# rokit.net
KiCad netlist of a schematic drawn in EAGLE
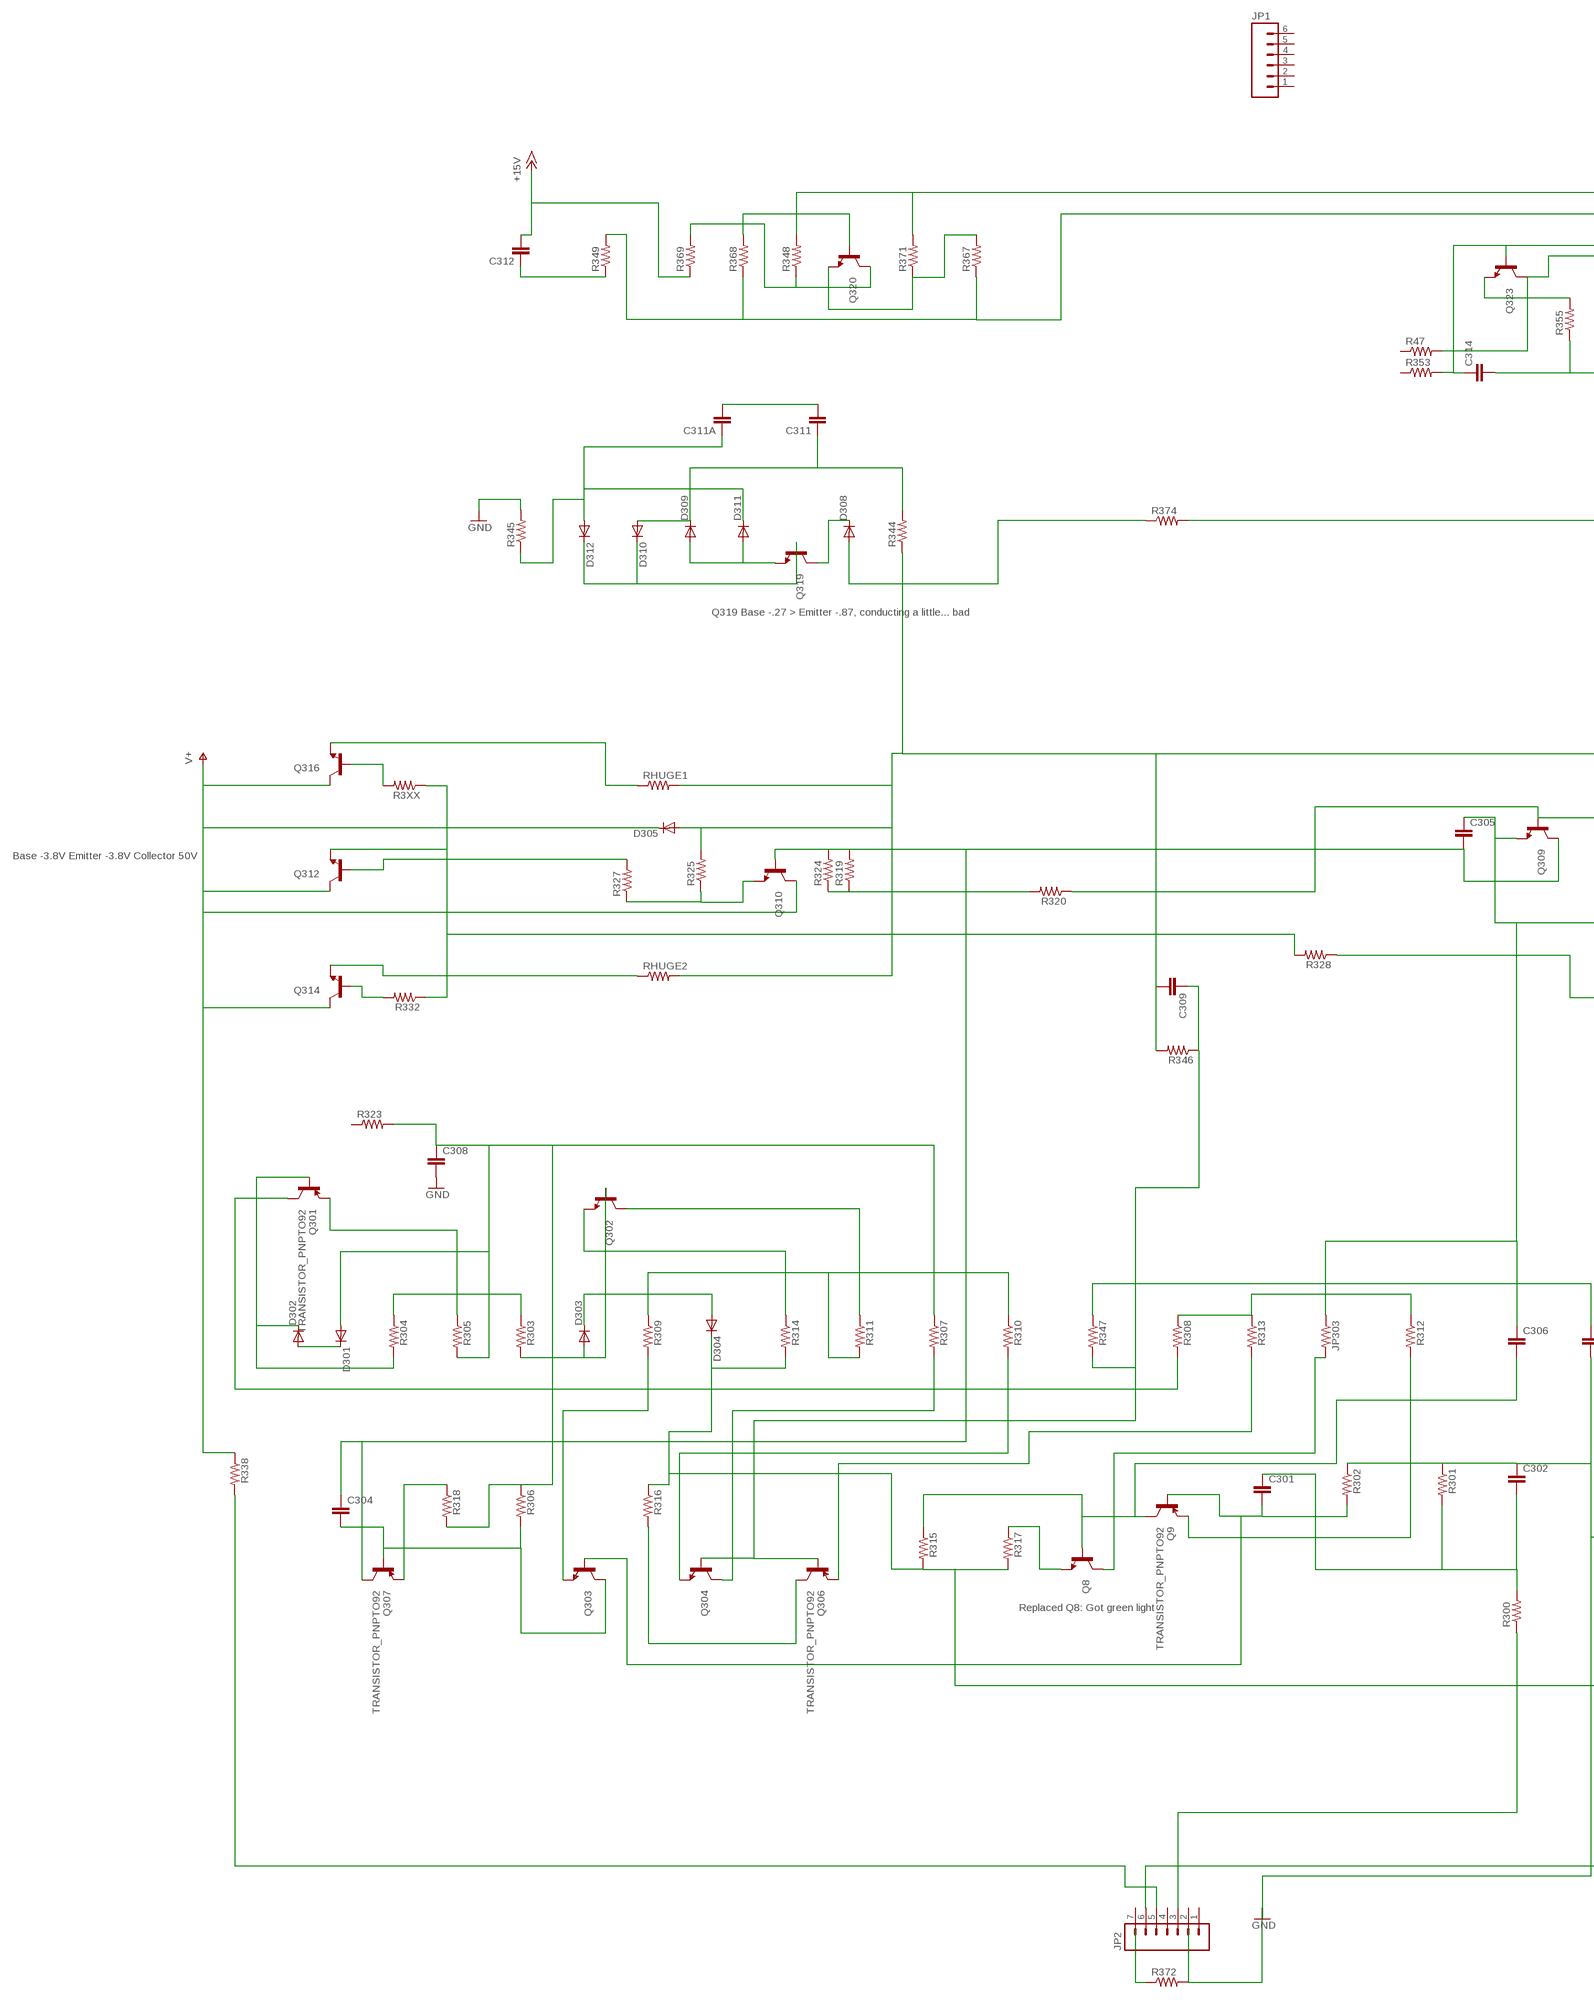
[diagram p0: schematic, sheet 1, part 1 of 2]
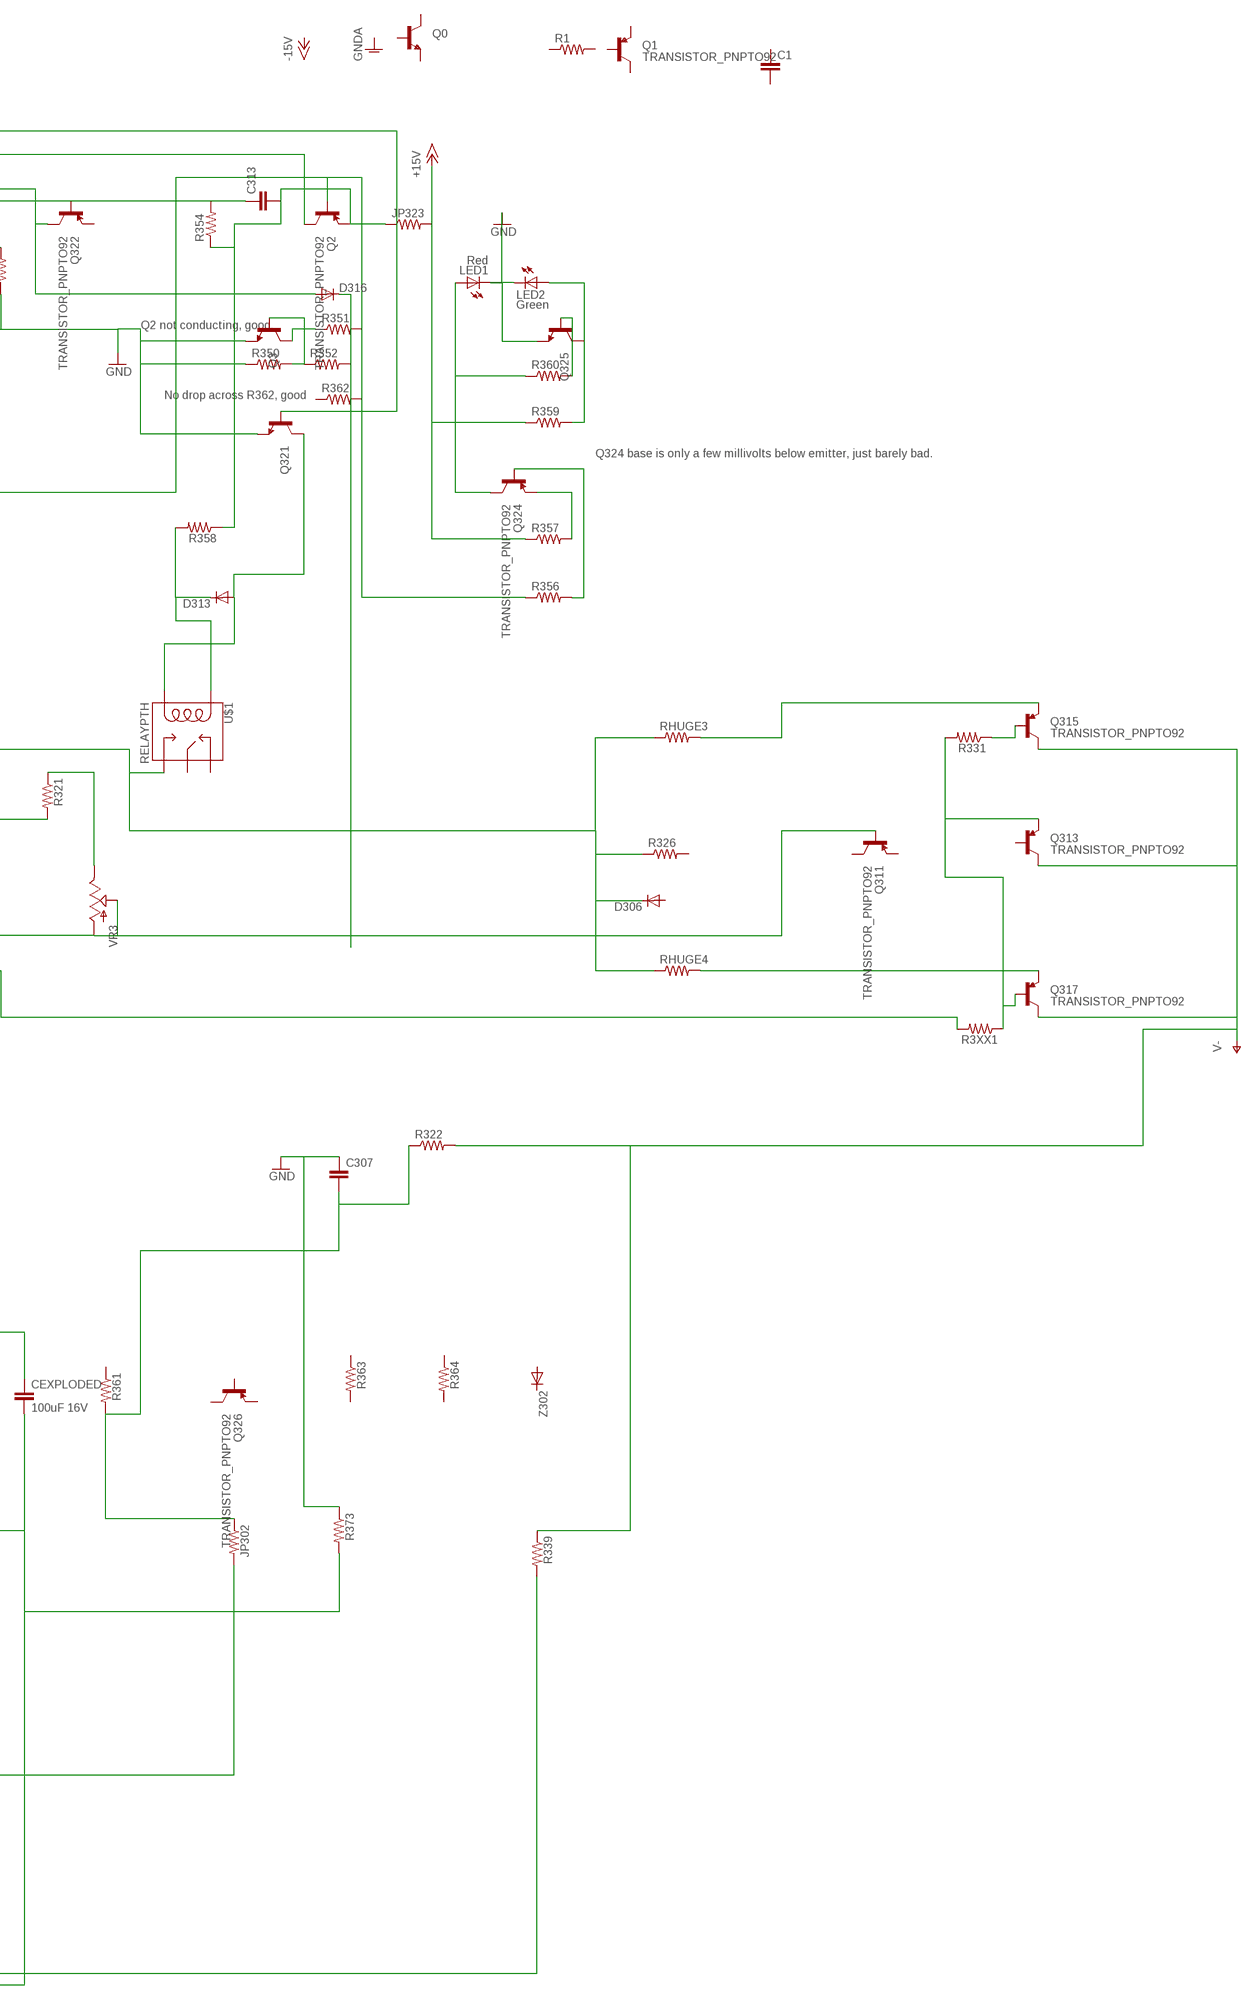
[diagram p1: schematic, sheet 1, part 2 of 2]

(export (version "E")
  (design (tool "Eeschema 10.0.6"))
  (components
    (comp (ref "C1")
      (value "CAPPTH")
      (footprint "eagle-import:CAP-PTH-SMALL")
      (libsource (lib "eagle-import") (part "CAPPTH"))
    )
    (comp (ref "C301")
      (value "CAPPTH")
      (footprint "eagle-import:CAP-PTH-SMALL")
      (libsource (lib "eagle-import") (part "CAPPTH"))
    )
    (comp (ref "C302")
      (value "CAPPTH")
      (footprint "eagle-import:CAP-PTH-SMALL")
      (libsource (lib "eagle-import") (part "CAPPTH"))
    )
    (comp (ref "C304")
      (value "CAPPTH")
      (footprint "eagle-import:CAP-PTH-SMALL")
      (libsource (lib "eagle-import") (part "CAPPTH"))
    )
    (comp (ref "C305")
      (value "CAPPTH")
      (footprint "eagle-import:CAP-PTH-SMALL")
      (libsource (lib "eagle-import") (part "CAPPTH"))
    )
    (comp (ref "C306")
      (value "CAPPTH")
      (footprint "eagle-import:CAP-PTH-SMALL")
      (libsource (lib "eagle-import") (part "CAPPTH"))
    )
    (comp (ref "C307")
      (value "CAPPTH")
      (footprint "eagle-import:CAP-PTH-SMALL")
      (libsource (lib "eagle-import") (part "CAPPTH"))
    )
    (comp (ref "C308")
      (value "CAPPTH")
      (footprint "eagle-import:CAP-PTH-SMALL")
      (libsource (lib "eagle-import") (part "CAPPTH"))
    )
    (comp (ref "C309")
      (value "CAPPTH")
      (footprint "eagle-import:CAP-PTH-SMALL")
      (libsource (lib "eagle-import") (part "CAPPTH"))
    )
    (comp (ref "C311")
      (value "CAPPTH")
      (footprint "eagle-import:CAP-PTH-SMALL")
      (libsource (lib "eagle-import") (part "CAPPTH"))
    )
    (comp (ref "C311A")
      (value "CAPPTH")
      (footprint "eagle-import:CAP-PTH-SMALL")
      (libsource (lib "eagle-import") (part "CAPPTH"))
    )
    (comp (ref "C312")
      (value "CAPPTH")
      (footprint "eagle-import:CAP-PTH-SMALL")
      (libsource (lib "eagle-import") (part "CAPPTH"))
    )
    (comp (ref "C313")
      (value "CAPPTH")
      (footprint "eagle-import:CAP-PTH-SMALL")
      (libsource (lib "eagle-import") (part "CAPPTH"))
    )
    (comp (ref "C314")
      (value "CAPPTH")
      (footprint "eagle-import:CAP-PTH-SMALL")
      (libsource (lib "eagle-import") (part "CAPPTH"))
    )
    (comp (ref "CEXPLODED")
      (value "100uF 16V")
      (footprint "eagle-import:CAP-PTH-SMALL")
      (libsource (lib "eagle-import") (part "CAPPTH"))
    )
    (comp (ref "D301")
      (value "DIODE1N4148")
      (footprint "eagle-import:DIODE-1N4148")
      (libsource (lib "eagle-import") (part "DIODE1N4148"))
    )
    (comp (ref "D302")
      (value "DIODE1N4148")
      (footprint "eagle-import:DIODE-1N4148")
      (libsource (lib "eagle-import") (part "DIODE1N4148"))
    )
    (comp (ref "D303")
      (value "DIODE1N4148")
      (footprint "eagle-import:DIODE-1N4148")
      (libsource (lib "eagle-import") (part "DIODE1N4148"))
    )
    (comp (ref "D304")
      (value "DIODE1N4148")
      (footprint "eagle-import:DIODE-1N4148")
      (libsource (lib "eagle-import") (part "DIODE1N4148"))
    )
    (comp (ref "D305")
      (value "DIODE1N4148")
      (footprint "eagle-import:DIODE-1N4148")
      (libsource (lib "eagle-import") (part "DIODE1N4148"))
    )
    (comp (ref "D306")
      (value "DIODE1N4148")
      (footprint "eagle-import:DIODE-1N4148")
      (libsource (lib "eagle-import") (part "DIODE1N4148"))
    )
    (comp (ref "D308")
      (value "DIODE1N4148")
      (footprint "eagle-import:DIODE-1N4148")
      (libsource (lib "eagle-import") (part "DIODE1N4148"))
    )
    (comp (ref "D309")
      (value "DIODE1N4148")
      (footprint "eagle-import:DIODE-1N4148")
      (libsource (lib "eagle-import") (part "DIODE1N4148"))
    )
    (comp (ref "D310")
      (value "DIODE1N4148")
      (footprint "eagle-import:DIODE-1N4148")
      (libsource (lib "eagle-import") (part "DIODE1N4148"))
    )
    (comp (ref "D311")
      (value "DIODE1N4148")
      (footprint "eagle-import:DIODE-1N4148")
      (libsource (lib "eagle-import") (part "DIODE1N4148"))
    )
    (comp (ref "D312")
      (value "DIODE1N4148")
      (footprint "eagle-import:DIODE-1N4148")
      (libsource (lib "eagle-import") (part "DIODE1N4148"))
    )
    (comp (ref "D313")
      (value "DIODE1N4148")
      (footprint "eagle-import:DIODE-1N4148")
      (libsource (lib "eagle-import") (part "DIODE1N4148"))
    )
    (comp (ref "D316")
      (value "DIODE1N4148")
      (footprint "eagle-import:DIODE-1N4148")
      (libsource (lib "eagle-import") (part "DIODE1N4148"))
    )
    (comp (ref "JP1")
      (value "M06LONGPADS")
      (footprint "eagle-import:1X06_LONGPADS")
      (libsource (lib "eagle-import") (part "M06LONGPADS"))
    )
    (comp (ref "JP2")
      (value "M07")
      (footprint "eagle-import:1X07")
      (libsource (lib "eagle-import") (part "M07"))
    )
    (comp (ref "JP302")
      (value "RESISTORPTH-1/4W")
      (footprint "eagle-import:AXIAL-0.4")
      (libsource (lib "eagle-import") (part "RESISTORPTH-1/4W"))
    )
    (comp (ref "JP303")
      (value "RESISTORPTH-1/4W")
      (footprint "eagle-import:AXIAL-0.4")
      (libsource (lib "eagle-import") (part "RESISTORPTH-1/4W"))
    )
    (comp (ref "JP323")
      (value "RESISTORPTH-1/4W")
      (footprint "eagle-import:AXIAL-0.4")
      (libsource (lib "eagle-import") (part "RESISTORPTH-1/4W"))
    )
    (comp (ref "LED1")
      (value "Red")
      (footprint "eagle-import:LED5MM")
      (libsource (lib "eagle-import") (part "LED5MM"))
    )
    (comp (ref "LED2")
      (value "Green")
      (footprint "eagle-import:LED5MM")
      (libsource (lib "eagle-import") (part "LED5MM"))
    )
    (comp (ref "Q0")
      (value "TRANSISTOR_NPNTO92")
      (footprint "eagle-import:TO-92")
      (libsource (lib "eagle-import") (part "TRANSISTOR_NPNTO92"))
    )
    (comp (ref "Q1")
      (value "TRANSISTOR_PNPTO92")
      (footprint "eagle-import:TO-92")
      (libsource (lib "eagle-import") (part "TRANSISTOR_PNPTO92"))
    )
    (comp (ref "Q2")
      (value "TRANSISTOR_PNPTO92")
      (footprint "eagle-import:TO-92")
      (libsource (lib "eagle-import") (part "TRANSISTOR_PNPTO92"))
    )
    (comp (ref "Q3")
      (value "TRANSISTOR_NPNTO92")
      (footprint "eagle-import:TO-92")
      (libsource (lib "eagle-import") (part "TRANSISTOR_NPNTO92"))
    )
    (comp (ref "Q8")
      (value "TRANSISTOR_NPNTO92")
      (footprint "eagle-import:TO-92")
      (libsource (lib "eagle-import") (part "TRANSISTOR_NPNTO92"))
    )
    (comp (ref "Q9")
      (value "TRANSISTOR_PNPTO92")
      (footprint "eagle-import:TO-92")
      (libsource (lib "eagle-import") (part "TRANSISTOR_PNPTO92"))
    )
    (comp (ref "Q301")
      (value "TRANSISTOR_PNPTO92")
      (footprint "eagle-import:TO-92")
      (libsource (lib "eagle-import") (part "TRANSISTOR_PNPTO92"))
    )
    (comp (ref "Q302")
      (value "TRANSISTOR_NPNTO92")
      (footprint "eagle-import:TO-92")
      (libsource (lib "eagle-import") (part "TRANSISTOR_NPNTO92"))
    )
    (comp (ref "Q303")
      (value "TRANSISTOR_NPNTO92")
      (footprint "eagle-import:TO-92")
      (libsource (lib "eagle-import") (part "TRANSISTOR_NPNTO92"))
    )
    (comp (ref "Q304")
      (value "TRANSISTOR_NPNTO92")
      (footprint "eagle-import:TO-92")
      (libsource (lib "eagle-import") (part "TRANSISTOR_NPNTO92"))
    )
    (comp (ref "Q306")
      (value "TRANSISTOR_PNPTO92")
      (footprint "eagle-import:TO-92")
      (libsource (lib "eagle-import") (part "TRANSISTOR_PNPTO92"))
    )
    (comp (ref "Q307")
      (value "TRANSISTOR_PNPTO92")
      (footprint "eagle-import:TO-92")
      (libsource (lib "eagle-import") (part "TRANSISTOR_PNPTO92"))
    )
    (comp (ref "Q309")
      (value "TRANSISTOR_NPNTO92")
      (footprint "eagle-import:TO-92")
      (libsource (lib "eagle-import") (part "TRANSISTOR_NPNTO92"))
    )
    (comp (ref "Q310")
      (value "TRANSISTOR_NPNTO92")
      (footprint "eagle-import:TO-92")
      (libsource (lib "eagle-import") (part "TRANSISTOR_NPNTO92"))
    )
    (comp (ref "Q311")
      (value "TRANSISTOR_PNPTO92")
      (footprint "eagle-import:TO-92")
      (libsource (lib "eagle-import") (part "TRANSISTOR_PNPTO92"))
    )
    (comp (ref "Q312")
      (value "TRANSISTOR_NPNTO92")
      (footprint "eagle-import:TO-92")
      (libsource (lib "eagle-import") (part "TRANSISTOR_NPNTO92"))
    )
    (comp (ref "Q313")
      (value "TRANSISTOR_PNPTO92")
      (footprint "eagle-import:TO-92")
      (libsource (lib "eagle-import") (part "TRANSISTOR_PNPTO92"))
    )
    (comp (ref "Q314")
      (value "TRANSISTOR_NPNTO92")
      (footprint "eagle-import:TO-92")
      (libsource (lib "eagle-import") (part "TRANSISTOR_NPNTO92"))
    )
    (comp (ref "Q315")
      (value "TRANSISTOR_PNPTO92")
      (footprint "eagle-import:TO-92")
      (libsource (lib "eagle-import") (part "TRANSISTOR_PNPTO92"))
    )
    (comp (ref "Q316")
      (value "TRANSISTOR_NPNTO92")
      (footprint "eagle-import:TO-92")
      (libsource (lib "eagle-import") (part "TRANSISTOR_NPNTO92"))
    )
    (comp (ref "Q317")
      (value "TRANSISTOR_PNPTO92")
      (footprint "eagle-import:TO-92")
      (libsource (lib "eagle-import") (part "TRANSISTOR_PNPTO92"))
    )
    (comp (ref "Q319")
      (value "TRANSISTOR_NPNTO92")
      (footprint "eagle-import:TO-92")
      (libsource (lib "eagle-import") (part "TRANSISTOR_NPNTO92"))
    )
    (comp (ref "Q320")
      (value "TRANSISTOR_NPNTO92")
      (footprint "eagle-import:TO-92")
      (libsource (lib "eagle-import") (part "TRANSISTOR_NPNTO92"))
    )
    (comp (ref "Q321")
      (value "TRANSISTOR_NPNTO92")
      (footprint "eagle-import:TO-92")
      (libsource (lib "eagle-import") (part "TRANSISTOR_NPNTO92"))
    )
    (comp (ref "Q322")
      (value "TRANSISTOR_PNPTO92")
      (footprint "eagle-import:TO-92")
      (libsource (lib "eagle-import") (part "TRANSISTOR_PNPTO92"))
    )
    (comp (ref "Q323")
      (value "TRANSISTOR_NPNTO92")
      (footprint "eagle-import:TO-92")
      (libsource (lib "eagle-import") (part "TRANSISTOR_NPNTO92"))
    )
    (comp (ref "Q324")
      (value "TRANSISTOR_PNPTO92")
      (footprint "eagle-import:TO-92")
      (libsource (lib "eagle-import") (part "TRANSISTOR_PNPTO92"))
    )
    (comp (ref "Q325")
      (value "TRANSISTOR_NPNTO92")
      (footprint "eagle-import:TO-92")
      (libsource (lib "eagle-import") (part "TRANSISTOR_NPNTO92"))
    )
    (comp (ref "Q326")
      (value "TRANSISTOR_PNPTO92")
      (footprint "eagle-import:TO-92")
      (libsource (lib "eagle-import") (part "TRANSISTOR_PNPTO92"))
    )
    (comp (ref "R1")
      (value "RESISTORPTH-1/4W")
      (footprint "eagle-import:AXIAL-0.4")
      (libsource (lib "eagle-import") (part "RESISTORPTH-1/4W"))
    )
    (comp (ref "R3XX")
      (value "RESISTORPTH-1/4W")
      (footprint "eagle-import:AXIAL-0.4")
      (libsource (lib "eagle-import") (part "RESISTORPTH-1/4W"))
    )
    (comp (ref "R3XX1")
      (value "RESISTORPTH-1/4W")
      (footprint "eagle-import:AXIAL-0.4")
      (libsource (lib "eagle-import") (part "RESISTORPTH-1/4W"))
    )
    (comp (ref "R47")
      (value "RESISTORPTH-1/4W")
      (footprint "eagle-import:AXIAL-0.4")
      (libsource (lib "eagle-import") (part "RESISTORPTH-1/4W"))
    )
    (comp (ref "R300")
      (value "RESISTORPTH-1/4W")
      (footprint "eagle-import:AXIAL-0.4")
      (libsource (lib "eagle-import") (part "RESISTORPTH-1/4W"))
    )
    (comp (ref "R301")
      (value "RESISTORPTH-1/4W")
      (footprint "eagle-import:AXIAL-0.4")
      (libsource (lib "eagle-import") (part "RESISTORPTH-1/4W"))
    )
    (comp (ref "R302")
      (value "RESISTORPTH-1/4W")
      (footprint "eagle-import:AXIAL-0.4")
      (libsource (lib "eagle-import") (part "RESISTORPTH-1/4W"))
    )
    (comp (ref "R303")
      (value "RESISTORPTH-1/4W")
      (footprint "eagle-import:AXIAL-0.4")
      (libsource (lib "eagle-import") (part "RESISTORPTH-1/4W"))
    )
    (comp (ref "R304")
      (value "RESISTORPTH-1/4W")
      (footprint "eagle-import:AXIAL-0.4")
      (libsource (lib "eagle-import") (part "RESISTORPTH-1/4W"))
    )
    (comp (ref "R305")
      (value "RESISTORPTH-1/4W")
      (footprint "eagle-import:AXIAL-0.4")
      (libsource (lib "eagle-import") (part "RESISTORPTH-1/4W"))
    )
    (comp (ref "R306")
      (value "RESISTORPTH-1/4W")
      (footprint "eagle-import:AXIAL-0.4")
      (libsource (lib "eagle-import") (part "RESISTORPTH-1/4W"))
    )
    (comp (ref "R307")
      (value "RESISTORPTH-1/4W")
      (footprint "eagle-import:AXIAL-0.4")
      (libsource (lib "eagle-import") (part "RESISTORPTH-1/4W"))
    )
    (comp (ref "R308")
      (value "RESISTORPTH-1/4W")
      (footprint "eagle-import:AXIAL-0.4")
      (libsource (lib "eagle-import") (part "RESISTORPTH-1/4W"))
    )
    (comp (ref "R309")
      (value "RESISTORPTH-1/4W")
      (footprint "eagle-import:AXIAL-0.4")
      (libsource (lib "eagle-import") (part "RESISTORPTH-1/4W"))
    )
    (comp (ref "R310")
      (value "RESISTORPTH-1/4W")
      (footprint "eagle-import:AXIAL-0.4")
      (libsource (lib "eagle-import") (part "RESISTORPTH-1/4W"))
    )
    (comp (ref "R311")
      (value "RESISTORPTH-1/4W")
      (footprint "eagle-import:AXIAL-0.4")
      (libsource (lib "eagle-import") (part "RESISTORPTH-1/4W"))
    )
    (comp (ref "R312")
      (value "RESISTORPTH-1/4W")
      (footprint "eagle-import:AXIAL-0.4")
      (libsource (lib "eagle-import") (part "RESISTORPTH-1/4W"))
    )
    (comp (ref "R313")
      (value "RESISTORPTH-1/4W")
      (footprint "eagle-import:AXIAL-0.4")
      (libsource (lib "eagle-import") (part "RESISTORPTH-1/4W"))
    )
    (comp (ref "R314")
      (value "RESISTORPTH-1/4W")
      (footprint "eagle-import:AXIAL-0.4")
      (libsource (lib "eagle-import") (part "RESISTORPTH-1/4W"))
    )
    (comp (ref "R315")
      (value "RESISTORPTH-1/4W")
      (footprint "eagle-import:AXIAL-0.4")
      (libsource (lib "eagle-import") (part "RESISTORPTH-1/4W"))
    )
    (comp (ref "R316")
      (value "RESISTORPTH-1/4W")
      (footprint "eagle-import:AXIAL-0.4")
      (libsource (lib "eagle-import") (part "RESISTORPTH-1/4W"))
    )
    (comp (ref "R317")
      (value "RESISTORPTH-1/4W")
      (footprint "eagle-import:AXIAL-0.4")
      (libsource (lib "eagle-import") (part "RESISTORPTH-1/4W"))
    )
    (comp (ref "R318")
      (value "RESISTORPTH-1/4W")
      (footprint "eagle-import:AXIAL-0.4")
      (libsource (lib "eagle-import") (part "RESISTORPTH-1/4W"))
    )
    (comp (ref "R319")
      (value "RESISTORPTH-1/4W")
      (footprint "eagle-import:AXIAL-0.4")
      (libsource (lib "eagle-import") (part "RESISTORPTH-1/4W"))
    )
    (comp (ref "R320")
      (value "RESISTORPTH-1/4W")
      (footprint "eagle-import:AXIAL-0.4")
      (libsource (lib "eagle-import") (part "RESISTORPTH-1/4W"))
    )
    (comp (ref "R321")
      (value "RESISTORPTH-1/4W")
      (footprint "eagle-import:AXIAL-0.4")
      (libsource (lib "eagle-import") (part "RESISTORPTH-1/4W"))
    )
    (comp (ref "R322")
      (value "RESISTORPTH-1/4W")
      (footprint "eagle-import:AXIAL-0.4")
      (libsource (lib "eagle-import") (part "RESISTORPTH-1/4W"))
    )
    (comp (ref "R323")
      (value "RESISTORPTH-1/4W")
      (footprint "eagle-import:AXIAL-0.4")
      (libsource (lib "eagle-import") (part "RESISTORPTH-1/4W"))
    )
    (comp (ref "R324")
      (value "RESISTORPTH-1/4W")
      (footprint "eagle-import:AXIAL-0.4")
      (libsource (lib "eagle-import") (part "RESISTORPTH-1/4W"))
    )
    (comp (ref "R325")
      (value "RESISTORPTH-1/4W")
      (footprint "eagle-import:AXIAL-0.4")
      (libsource (lib "eagle-import") (part "RESISTORPTH-1/4W"))
    )
    (comp (ref "R326")
      (value "RESISTORPTH-1/4W")
      (footprint "eagle-import:AXIAL-0.4")
      (libsource (lib "eagle-import") (part "RESISTORPTH-1/4W"))
    )
    (comp (ref "R327")
      (value "RESISTORPTH-1/4W")
      (footprint "eagle-import:AXIAL-0.4")
      (libsource (lib "eagle-import") (part "RESISTORPTH-1/4W"))
    )
    (comp (ref "R328")
      (value "RESISTORPTH-1/4W")
      (footprint "eagle-import:AXIAL-0.4")
      (libsource (lib "eagle-import") (part "RESISTORPTH-1/4W"))
    )
    (comp (ref "R331")
      (value "RESISTORPTH-1/4W")
      (footprint "eagle-import:AXIAL-0.4")
      (libsource (lib "eagle-import") (part "RESISTORPTH-1/4W"))
    )
    (comp (ref "R332")
      (value "RESISTORPTH-1/4W")
      (footprint "eagle-import:AXIAL-0.4")
      (libsource (lib "eagle-import") (part "RESISTORPTH-1/4W"))
    )
    (comp (ref "R338")
      (value "RESISTORPTH-1/4W")
      (footprint "eagle-import:AXIAL-0.4")
      (libsource (lib "eagle-import") (part "RESISTORPTH-1/4W"))
    )
    (comp (ref "R339")
      (value "RESISTORPTH-1/4W")
      (footprint "eagle-import:AXIAL-0.4")
      (libsource (lib "eagle-import") (part "RESISTORPTH-1/4W"))
    )
    (comp (ref "R344")
      (value "RESISTORPTH-1/4W")
      (footprint "eagle-import:AXIAL-0.4")
      (libsource (lib "eagle-import") (part "RESISTORPTH-1/4W"))
    )
    (comp (ref "R345")
      (value "RESISTORPTH-1/4W")
      (footprint "eagle-import:AXIAL-0.4")
      (libsource (lib "eagle-import") (part "RESISTORPTH-1/4W"))
    )
    (comp (ref "R346")
      (value "RESISTORPTH-1/4W")
      (footprint "eagle-import:AXIAL-0.4")
      (libsource (lib "eagle-import") (part "RESISTORPTH-1/4W"))
    )
    (comp (ref "R347")
      (value "RESISTORPTH-1/4W")
      (footprint "eagle-import:AXIAL-0.4")
      (libsource (lib "eagle-import") (part "RESISTORPTH-1/4W"))
    )
    (comp (ref "R348")
      (value "RESISTORPTH-1/4W")
      (footprint "eagle-import:AXIAL-0.4")
      (libsource (lib "eagle-import") (part "RESISTORPTH-1/4W"))
    )
    (comp (ref "R349")
      (value "RESISTORPTH-1/4W")
      (footprint "eagle-import:AXIAL-0.4")
      (libsource (lib "eagle-import") (part "RESISTORPTH-1/4W"))
    )
    (comp (ref "R350")
      (value "RESISTORPTH-1/4W")
      (footprint "eagle-import:AXIAL-0.4")
      (libsource (lib "eagle-import") (part "RESISTORPTH-1/4W"))
    )
    (comp (ref "R351")
      (value "RESISTORPTH-1/4W")
      (footprint "eagle-import:AXIAL-0.4")
      (libsource (lib "eagle-import") (part "RESISTORPTH-1/4W"))
    )
    (comp (ref "R352")
      (value "RESISTORPTH-1/4W")
      (footprint "eagle-import:AXIAL-0.4")
      (libsource (lib "eagle-import") (part "RESISTORPTH-1/4W"))
    )
    (comp (ref "R353")
      (value "RESISTORPTH-1/4W")
      (footprint "eagle-import:AXIAL-0.4")
      (libsource (lib "eagle-import") (part "RESISTORPTH-1/4W"))
    )
    (comp (ref "R354")
      (value "RESISTORPTH-1/4W")
      (footprint "eagle-import:AXIAL-0.4")
      (libsource (lib "eagle-import") (part "RESISTORPTH-1/4W"))
    )
    (comp (ref "R355")
      (value "RESISTORPTH-1/4W")
      (footprint "eagle-import:AXIAL-0.4")
      (libsource (lib "eagle-import") (part "RESISTORPTH-1/4W"))
    )
    (comp (ref "R356")
      (value "RESISTORPTH-1/4W")
      (footprint "eagle-import:AXIAL-0.4")
      (libsource (lib "eagle-import") (part "RESISTORPTH-1/4W"))
    )
    (comp (ref "R357")
      (value "RESISTORPTH-1/4W")
      (footprint "eagle-import:AXIAL-0.4")
      (libsource (lib "eagle-import") (part "RESISTORPTH-1/4W"))
    )
    (comp (ref "R358")
      (value "RESISTORPTH-1/4W")
      (footprint "eagle-import:AXIAL-0.4")
      (libsource (lib "eagle-import") (part "RESISTORPTH-1/4W"))
    )
    (comp (ref "R359")
      (value "RESISTORPTH-1/4W")
      (footprint "eagle-import:AXIAL-0.4")
      (libsource (lib "eagle-import") (part "RESISTORPTH-1/4W"))
    )
    (comp (ref "R360")
      (value "RESISTORPTH-1/4W")
      (footprint "eagle-import:AXIAL-0.4")
      (libsource (lib "eagle-import") (part "RESISTORPTH-1/4W"))
    )
    (comp (ref "R361")
      (value "RESISTORPTH-1/4W")
      (footprint "eagle-import:AXIAL-0.4")
      (libsource (lib "eagle-import") (part "RESISTORPTH-1/4W"))
    )
    (comp (ref "R362")
      (value "RESISTORPTH-1/4W")
      (footprint "eagle-import:AXIAL-0.4")
      (libsource (lib "eagle-import") (part "RESISTORPTH-1/4W"))
    )
    (comp (ref "R363")
      (value "RESISTORPTH-1/4W")
      (footprint "eagle-import:AXIAL-0.4")
      (libsource (lib "eagle-import") (part "RESISTORPTH-1/4W"))
    )
    (comp (ref "R364")
      (value "RESISTORPTH-1/4W")
      (footprint "eagle-import:AXIAL-0.4")
      (libsource (lib "eagle-import") (part "RESISTORPTH-1/4W"))
    )
    (comp (ref "R367")
      (value "RESISTORPTH-1/4W")
      (footprint "eagle-import:AXIAL-0.4")
      (libsource (lib "eagle-import") (part "RESISTORPTH-1/4W"))
    )
    (comp (ref "R368")
      (value "RESISTORPTH-1/4W")
      (footprint "eagle-import:AXIAL-0.4")
      (libsource (lib "eagle-import") (part "RESISTORPTH-1/4W"))
    )
    (comp (ref "R369")
      (value "RESISTORPTH-1/4W")
      (footprint "eagle-import:AXIAL-0.4")
      (libsource (lib "eagle-import") (part "RESISTORPTH-1/4W"))
    )
    (comp (ref "R371")
      (value "RESISTORPTH-1/4W")
      (footprint "eagle-import:AXIAL-0.4")
      (libsource (lib "eagle-import") (part "RESISTORPTH-1/4W"))
    )
    (comp (ref "R372")
      (value "RESISTORPTH-1/4W")
      (footprint "eagle-import:AXIAL-0.4")
      (libsource (lib "eagle-import") (part "RESISTORPTH-1/4W"))
    )
    (comp (ref "R373")
      (value "RESISTORPTH-1/4W")
      (footprint "eagle-import:AXIAL-0.4")
      (libsource (lib "eagle-import") (part "RESISTORPTH-1/4W"))
    )
    (comp (ref "R374")
      (value "RESISTORPTH-1/4W")
      (footprint "eagle-import:AXIAL-0.4")
      (libsource (lib "eagle-import") (part "RESISTORPTH-1/4W"))
    )
    (comp (ref "RHUGE1")
      (value "RESISTORPTH-1/4W")
      (footprint "eagle-import:AXIAL-0.4")
      (libsource (lib "eagle-import") (part "RESISTORPTH-1/4W"))
    )
    (comp (ref "RHUGE2")
      (value "RESISTORPTH-1/4W")
      (footprint "eagle-import:AXIAL-0.4")
      (libsource (lib "eagle-import") (part "RESISTORPTH-1/4W"))
    )
    (comp (ref "RHUGE3")
      (value "RESISTORPTH-1/4W")
      (footprint "eagle-import:AXIAL-0.4")
      (libsource (lib "eagle-import") (part "RESISTORPTH-1/4W"))
    )
    (comp (ref "RHUGE4")
      (value "RESISTORPTH-1/4W")
      (footprint "eagle-import:AXIAL-0.4")
      (libsource (lib "eagle-import") (part "RESISTORPTH-1/4W"))
    )
    (comp (ref "U$1")
      (value "RELAYPTH")
      (footprint "eagle-import:RELAY-G5Q")
      (libsource (lib "eagle-import") (part "RELAYPTH"))
    )
    (comp (ref "VR3")
      (value "POTTRIM")
      (footprint "eagle-import:TRIM_POT")
      (libsource (lib "eagle-import") (part "POTTRIM"))
    )
    (comp (ref "Z302")
      (value "DIODE1N4148")
      (footprint "eagle-import:DIODE-1N4148")
      (libsource (lib "eagle-import") (part "DIODE1N4148"))
    )
  )
  (nets
    (net (code "1") (name "+15V") (class "Default")
      (node (ref "C312") (pin "2") (pinfunction "2_2") (pintype "passive"))
      (node (ref "JP323") (pin "P$2") (pinfunction "2_P$2") (pintype "passive"))
      (node (ref "R357") (pin "P$1") (pinfunction "1_P$1") (pintype "passive"))
      (node (ref "R359") (pin "P$1") (pinfunction "1_P$1") (pintype "passive"))
      (node (ref "R369") (pin "P$1") (pinfunction "1_P$1") (pintype "passive"))
    )
    (net (code "3") (name "GND") (class "Default")
      (node (ref "C302") (pin "1") (pinfunction "1_1") (pintype "passive"))
      (node (ref "C307") (pin "1") (pinfunction "1_1") (pintype "passive"))
      (node (ref "C308") (pin "2") (pinfunction "2_2") (pintype "passive"))
      (node (ref "C314") (pin "2") (pinfunction "2_2") (pintype "passive"))
      (node (ref "CEXPLODED") (pin "2") (pinfunction "2_2") (pintype "passive"))
      (node (ref "LED1") (pin "K") (pinfunction "C_K") (pintype "passive"))
      (node (ref "LED2") (pin "K") (pinfunction "C_K") (pintype "passive"))
      (node (ref "Q3") (pin "1") (pinfunction "E_1") (pintype "passive"))
      (node (ref "Q321") (pin "1") (pinfunction "E_1") (pintype "passive"))
      (node (ref "Q325") (pin "1") (pinfunction "E_1") (pintype "passive"))
      (node (ref "R301") (pin "P$1") (pinfunction "1_P$1") (pintype "passive"))
      (node (ref "R302") (pin "P$1") (pinfunction "1_P$1") (pintype "passive"))
      (node (ref "R345") (pin "P$2") (pinfunction "2_P$2") (pintype "passive"))
      (node (ref "R350") (pin "P$1") (pinfunction "1_P$1") (pintype "passive"))
      (node (ref "R355") (pin "P$1") (pinfunction "1_P$1") (pintype "passive"))
      (node (ref "R372") (pin "P$2") (pinfunction "2_P$2") (pintype "passive"))
      (node (ref "R373") (pin "P$1") (pinfunction "1_P$1") (pintype "passive"))
      (node (ref "R373") (pin "P$2") (pinfunction "2_P$2") (pintype "passive"))
    )
    (net (code "5") (name "Net-(C311-Pad2)") (class "Default")
      (node (ref "C311") (pin "2") (pinfunction "2_2") (pintype "passive"))
      (node (ref "C311A") (pin "2") (pinfunction "2_2") (pintype "passive"))
    )
    (net (code "6") (name "Net-(D301-PadC)") (class "Default")
      (node (ref "D301") (pin "C") (pinfunction "C_C") (pintype "passive"))
      (node (ref "D302") (pin "A") (pinfunction "A_A") (pintype "passive"))
    )
    (net (code "7") (name "Net-(D303-PadC)") (class "Default")
      (node (ref "D303") (pin "C") (pinfunction "C_C") (pintype "passive"))
      (node (ref "D304") (pin "A") (pinfunction "A_A") (pintype "passive"))
    )
    (net (code "8") (name "Net-(JP302-1)") (class "Default")
      (node (ref "C307") (pin "2") (pinfunction "2_2") (pintype "passive"))
      (node (ref "JP302") (pin "P$1") (pinfunction "1_P$1") (pintype "passive"))
      (node (ref "R322") (pin "P$1") (pinfunction "1_P$1") (pintype "passive"))
      (node (ref "R361") (pin "P$2") (pinfunction "2_P$2") (pintype "passive"))
    )
    (net (code "9") (name "Net-(JP302-2)") (class "Default")
      (node (ref "D304") (pin "C") (pinfunction "C_C") (pintype "passive"))
      (node (ref "JP302") (pin "P$2") (pinfunction "2_P$2") (pintype "passive"))
      (node (ref "R314") (pin "P$2") (pinfunction "2_P$2") (pintype "passive"))
      (node (ref "R315") (pin "P$2") (pinfunction "2_P$2") (pintype "passive"))
      (node (ref "R316") (pin "P$1") (pinfunction "1_P$1") (pintype "passive"))
      (node (ref "R317") (pin "P$2") (pinfunction "2_P$2") (pintype "passive"))
    )
    (net (code "10") (name "Net-(JP303-1)") (class "Default")
      (node (ref "C305") (pin "1") (pinfunction "1_1") (pintype "passive"))
      (node (ref "C306") (pin "1") (pinfunction "1_1") (pintype "passive"))
      (node (ref "JP303") (pin "P$1") (pinfunction "1_P$1") (pintype "passive"))
      (node (ref "Q309") (pin "1") (pinfunction "E_1") (pintype "passive"))
      (node (ref "Q311") (pin "2") (pinfunction "B_2") (pintype "passive"))
      (node (ref "VR3") (pin "1") (pinfunction "S_1") (pintype "passive"))
      (node (ref "VR3") (pin "3") (pinfunction "A_3") (pintype "passive"))
    )
    (net (code "11") (name "Net-(JP303-2)") (class "Default")
      (node (ref "JP303") (pin "P$2") (pinfunction "2_P$2") (pintype "passive"))
      (node (ref "Q8") (pin "3") (pinfunction "C_3") (pintype "passive"))
    )
    (net (code "12") (name "Net-(JP323-1)") (class "Default")
      (node (ref "C313") (pin "2") (pinfunction "2_2") (pintype "passive"))
      (node (ref "JP323") (pin "P$1") (pinfunction "1_P$1") (pintype "passive"))
      (node (ref "Q2") (pin "1") (pinfunction "E_1") (pintype "passive"))
      (node (ref "R354") (pin "P$1") (pinfunction "1_P$1") (pintype "passive"))
      (node (ref "R358") (pin "P$1") (pinfunction "1_P$1") (pintype "passive"))
    )
    (net (code "13") (name "Net-(Q2-B)") (class "Default")
      (node (ref "Q2") (pin "2") (pinfunction "B_2") (pintype "passive"))
      (node (ref "R351") (pin "P$2") (pinfunction "2_P$2") (pintype "passive"))
      (node (ref "R356") (pin "P$1") (pinfunction "1_P$1") (pintype "passive"))
      (node (ref "R362") (pin "P$2") (pinfunction "2_P$2") (pintype "passive"))
      (node (ref "R374") (pin "P$2") (pinfunction "2_P$2") (pintype "passive"))
    )
    (net (code "14") (name "Net-(Q2-C)") (class "Default")
      (node (ref "Q2") (pin "3") (pinfunction "C_3") (pintype "passive"))
      (node (ref "R349") (pin "P$2") (pinfunction "2_P$2") (pintype "passive"))
      (node (ref "R367") (pin "P$1") (pinfunction "1_P$1") (pintype "passive"))
      (node (ref "R368") (pin "P$1") (pinfunction "1_P$1") (pintype "passive"))
    )
    (net (code "15") (name "Net-(Q3-B)") (class "Default")
      (node (ref "Q3") (pin "2") (pinfunction "B_2") (pintype "passive"))
      (node (ref "R350") (pin "P$2") (pinfunction "2_P$2") (pintype "passive"))
      (node (ref "R352") (pin "P$1") (pinfunction "1_P$1") (pintype "passive"))
    )
    (net (code "16") (name "Net-(Q3-C)") (class "Default")
      (node (ref "Q3") (pin "3") (pinfunction "C_3") (pintype "passive"))
      (node (ref "R351") (pin "P$1") (pinfunction "1_P$1") (pintype "passive"))
    )
    (net (code "17") (name "Net-(Q8-B)") (class "Default")
      (node (ref "C306") (pin "2") (pinfunction "2_2") (pintype "passive"))
      (node (ref "Q8") (pin "2") (pinfunction "B_2") (pintype "passive"))
      (node (ref "Q9") (pin "3") (pinfunction "C_3") (pintype "passive"))
      (node (ref "R315") (pin "P$1") (pinfunction "1_P$1") (pintype "passive"))
    )
    (net (code "18") (name "Net-(Q8-E)") (class "Default")
      (node (ref "Q8") (pin "1") (pinfunction "E_1") (pintype "passive"))
      (node (ref "R317") (pin "P$1") (pinfunction "1_P$1") (pintype "passive"))
    )
    (net (code "19") (name "Net-(Q9-E)") (class "Default")
      (node (ref "Q9") (pin "1") (pinfunction "E_1") (pintype "passive"))
      (node (ref "R312") (pin "P$2") (pinfunction "2_P$2") (pintype "passive"))
    )
    (net (code "20") (name "Net-(Q301-B)") (class "Default")
      (node (ref "D302") (pin "C") (pinfunction "C_C") (pintype "passive"))
      (node (ref "Q301") (pin "2") (pinfunction "B_2") (pintype "passive"))
      (node (ref "R304") (pin "P$2") (pinfunction "2_P$2") (pintype "passive"))
    )
    (net (code "21") (name "Net-(Q301-C)") (class "Default")
      (node (ref "Q301") (pin "3") (pinfunction "C_3") (pintype "passive"))
      (node (ref "R308") (pin "P$2") (pinfunction "2_P$2") (pintype "passive"))
    )
    (net (code "22") (name "Net-(Q301-E)") (class "Default")
      (node (ref "Q301") (pin "1") (pinfunction "E_1") (pintype "passive"))
      (node (ref "R305") (pin "P$1") (pinfunction "1_P$1") (pintype "passive"))
    )
    (net (code "23") (name "Net-(Q302-B)") (class "Default")
      (node (ref "D303") (pin "A") (pinfunction "A_A") (pintype "passive"))
      (node (ref "Q302") (pin "2") (pinfunction "B_2") (pintype "passive"))
      (node (ref "R303") (pin "P$2") (pinfunction "2_P$2") (pintype "passive"))
    )
    (net (code "24") (name "Net-(Q302-C)") (class "Default")
      (node (ref "Q302") (pin "3") (pinfunction "C_3") (pintype "passive"))
      (node (ref "R311") (pin "P$1") (pinfunction "1_P$1") (pintype "passive"))
    )
    (net (code "25") (name "Net-(Q302-E)") (class "Default")
      (node (ref "Q302") (pin "1") (pinfunction "E_1") (pintype "passive"))
      (node (ref "R314") (pin "P$1") (pinfunction "1_P$1") (pintype "passive"))
    )
    (net (code "26") (name "Net-(Q303-B)") (class "Default")
      (node (ref "C301") (pin "2") (pinfunction "2_2") (pintype "passive"))
      (node (ref "Q303") (pin "2") (pinfunction "B_2") (pintype "passive"))
      (node (ref "Q9") (pin "2") (pinfunction "B_2") (pintype "passive"))
      (node (ref "R302") (pin "P$2") (pinfunction "2_P$2") (pintype "passive"))
    )
    (net (code "27") (name "Net-(Q303-C)") (class "Default")
      (node (ref "C304") (pin "2") (pinfunction "2_2") (pintype "passive"))
      (node (ref "Q303") (pin "3") (pinfunction "C_3") (pintype "passive"))
      (node (ref "Q307") (pin "2") (pinfunction "B_2") (pintype "passive"))
      (node (ref "R306") (pin "P$2") (pinfunction "2_P$2") (pintype "passive"))
    )
    (net (code "28") (name "Net-(Q303-E)") (class "Default")
      (node (ref "Q303") (pin "1") (pinfunction "E_1") (pintype "passive"))
      (node (ref "R309") (pin "P$2") (pinfunction "2_P$2") (pintype "passive"))
    )
    (net (code "29") (name "Net-(Q304-B)") (class "Default")
      (node (ref "C309") (pin "1") (pinfunction "1_1") (pintype "passive"))
      (node (ref "Q304") (pin "2") (pinfunction "B_2") (pintype "passive"))
      (node (ref "Q306") (pin "2") (pinfunction "B_2") (pintype "passive"))
      (node (ref "R346") (pin "P$1") (pinfunction "1_P$1") (pintype "passive"))
      (node (ref "R347") (pin "P$2") (pinfunction "2_P$2") (pintype "passive"))
    )
    (net (code "30") (name "Net-(Q304-C)") (class "Default")
      (node (ref "Q304") (pin "3") (pinfunction "C_3") (pintype "passive"))
      (node (ref "R307") (pin "P$2") (pinfunction "2_P$2") (pintype "passive"))
    )
    (net (code "31") (name "Net-(Q304-E)") (class "Default")
      (node (ref "Q304") (pin "1") (pinfunction "E_1") (pintype "passive"))
      (node (ref "R310") (pin "P$2") (pinfunction "2_P$2") (pintype "passive"))
    )
    (net (code "32") (name "Net-(Q306-C)") (class "Default")
      (node (ref "Q306") (pin "3") (pinfunction "C_3") (pintype "passive"))
      (node (ref "R316") (pin "P$2") (pinfunction "2_P$2") (pintype "passive"))
    )
    (net (code "33") (name "Net-(Q306-E)") (class "Default")
      (node (ref "Q306") (pin "1") (pinfunction "E_1") (pintype "passive"))
      (node (ref "R313") (pin "P$2") (pinfunction "2_P$2") (pintype "passive"))
    )
    (net (code "34") (name "Net-(Q307-C)") (class "Default")
      (node (ref "C304") (pin "1") (pinfunction "1_1") (pintype "passive"))
      (node (ref "C305") (pin "2") (pinfunction "2_2") (pintype "passive"))
      (node (ref "Q307") (pin "3") (pinfunction "C_3") (pintype "passive"))
      (node (ref "Q309") (pin "3") (pinfunction "C_3") (pintype "passive"))
      (node (ref "Q310") (pin "2") (pinfunction "B_2") (pintype "passive"))
      (node (ref "R319") (pin "P$2") (pinfunction "2_P$2") (pintype "passive"))
      (node (ref "R324") (pin "P$2") (pinfunction "2_P$2") (pintype "passive"))
    )
    (net (code "35") (name "Net-(Q307-E)") (class "Default")
      (node (ref "Q307") (pin "1") (pinfunction "E_1") (pintype "passive"))
      (node (ref "R318") (pin "P$1") (pinfunction "1_P$1") (pintype "passive"))
    )
    (net (code "36") (name "Net-(Q309-B)") (class "Default")
      (node (ref "Q309") (pin "2") (pinfunction "B_2") (pintype "passive"))
      (node (ref "R320") (pin "P$1") (pinfunction "1_P$1") (pintype "passive"))
      (node (ref "R321") (pin "P$2") (pinfunction "2_P$2") (pintype "passive"))
    )
    (net (code "37") (name "Net-(Q310-E)") (class "Default")
      (node (ref "Q310") (pin "1") (pinfunction "E_1") (pintype "passive"))
      (node (ref "R325") (pin "P$1") (pinfunction "1_P$1") (pintype "passive"))
      (node (ref "R327") (pin "P$1") (pinfunction "1_P$1") (pintype "passive"))
    )
    (net (code "38") (name "Net-(Q312-B)") (class "Default")
      (node (ref "Q312") (pin "2") (pinfunction "B_2") (pintype "passive"))
      (node (ref "R327") (pin "P$2") (pinfunction "2_P$2") (pintype "passive"))
    )
    (net (code "39") (name "Net-(Q312-E)") (class "Default")
      (node (ref "Q312") (pin "1") (pinfunction "E_1") (pintype "passive"))
      (node (ref "R328") (pin "P$2") (pinfunction "2_P$2") (pintype "passive"))
      (node (ref "R332") (pin "P$1") (pinfunction "1_P$1") (pintype "passive"))
      (node (ref "R3XX") (pin "P$1") (pinfunction "1_P$1") (pintype "passive"))
    )
    (net (code "40") (name "Net-(Q313-E)") (class "Default")
      (node (ref "Q313") (pin "1") (pinfunction "E_1") (pintype "passive"))
      (node (ref "Q317") (pin "2") (pinfunction "B_2") (pintype "passive"))
      (node (ref "R331") (pin "P$2") (pinfunction "2_P$2") (pintype "passive"))
      (node (ref "R3XX1") (pin "P$1") (pinfunction "1_P$1") (pintype "passive"))
    )
    (net (code "41") (name "Net-(Q314-B)") (class "Default")
      (node (ref "Q314") (pin "2") (pinfunction "B_2") (pintype "passive"))
      (node (ref "R332") (pin "P$2") (pinfunction "2_P$2") (pintype "passive"))
    )
    (net (code "42") (name "Net-(Q314-E)") (class "Default")
      (node (ref "Q314") (pin "1") (pinfunction "E_1") (pintype "passive"))
      (node (ref "RHUGE2") (pin "P$1") (pinfunction "1_P$1") (pintype "passive"))
    )
    (net (code "43") (name "Net-(Q315-B)") (class "Default")
      (node (ref "Q315") (pin "2") (pinfunction "B_2") (pintype "passive"))
      (node (ref "R331") (pin "P$1") (pinfunction "1_P$1") (pintype "passive"))
    )
    (net (code "44") (name "Net-(Q315-E)") (class "Default")
      (node (ref "Q315") (pin "1") (pinfunction "E_1") (pintype "passive"))
      (node (ref "RHUGE3") (pin "P$2") (pinfunction "2_P$2") (pintype "passive"))
    )
    (net (code "45") (name "Net-(Q316-B)") (class "Default")
      (node (ref "Q316") (pin "2") (pinfunction "B_2") (pintype "passive"))
      (node (ref "R3XX") (pin "P$2") (pinfunction "2_P$2") (pintype "passive"))
    )
    (net (code "46") (name "Net-(Q316-E)") (class "Default")
      (node (ref "Q316") (pin "1") (pinfunction "E_1") (pintype "passive"))
      (node (ref "RHUGE1") (pin "P$1") (pinfunction "1_P$1") (pintype "passive"))
    )
    (net (code "47") (name "Net-(Q317-E)") (class "Default")
      (node (ref "Q317") (pin "1") (pinfunction "E_1") (pintype "passive"))
      (node (ref "RHUGE4") (pin "P$2") (pinfunction "2_P$2") (pintype "passive"))
    )
    (net (code "48") (name "Net-(Q319-B)") (class "Default")
      (node (ref "D310") (pin "C") (pinfunction "C_C") (pintype "passive"))
      (node (ref "D312") (pin "C") (pinfunction "C_C") (pintype "passive"))
      (node (ref "Q319") (pin "2") (pinfunction "B_2") (pintype "passive"))
    )
    (net (code "49") (name "Net-(Q319-C)") (class "Default")
      (node (ref "D308") (pin "C") (pinfunction "C_C") (pintype "passive"))
      (node (ref "Q319") (pin "3") (pinfunction "C_3") (pintype "passive"))
    )
    (net (code "50") (name "Net-(Q319-E)") (class "Default")
      (node (ref "D309") (pin "A") (pinfunction "A_A") (pintype "passive"))
      (node (ref "D311") (pin "A") (pinfunction "A_A") (pintype "passive"))
      (node (ref "Q319") (pin "1") (pinfunction "E_1") (pintype "passive"))
    )
    (net (code "51") (name "Net-(Q320-B)") (class "Default")
      (node (ref "Q320") (pin "2") (pinfunction "B_2") (pintype "passive"))
      (node (ref "R368") (pin "P$2") (pinfunction "2_P$2") (pintype "passive"))
    )
    (net (code "52") (name "Net-(Q320-C)") (class "Default")
      (node (ref "Q320") (pin "3") (pinfunction "C_3") (pintype "passive"))
      (node (ref "R348") (pin "P$1") (pinfunction "1_P$1") (pintype "passive"))
      (node (ref "R369") (pin "P$2") (pinfunction "2_P$2") (pintype "passive"))
    )
    (net (code "53") (name "Net-(Q320-E)") (class "Default")
      (node (ref "Q320") (pin "1") (pinfunction "E_1") (pintype "passive"))
      (node (ref "R367") (pin "P$2") (pinfunction "2_P$2") (pintype "passive"))
      (node (ref "R371") (pin "P$1") (pinfunction "1_P$1") (pintype "passive"))
    )
    (net (code "54") (name "Net-(Q321-B)") (class "Default")
      (node (ref "Q321") (pin "2") (pinfunction "B_2") (pintype "passive"))
      (node (ref "R348") (pin "P$2") (pinfunction "2_P$2") (pintype "passive"))
      (node (ref "R371") (pin "P$2") (pinfunction "2_P$2") (pintype "passive"))
    )
    (net (code "55") (name "Net-(Q321-C)") (class "Default")
      (node (ref "D313") (pin "A") (pinfunction "A_A") (pintype "passive"))
      (node (ref "Q321") (pin "3") (pinfunction "C_3") (pintype "passive"))
      (node (ref "U$1") (pin "1") (pinfunction "COIL2_1") (pintype "bidirectional"))
    )
    (net (code "56") (name "Net-(Q322-B)") (class "Default")
      (node (ref "C313") (pin "1") (pinfunction "1_1") (pintype "passive"))
      (node (ref "Q322") (pin "2") (pinfunction "B_2") (pintype "passive"))
      (node (ref "Q323") (pin "3") (pinfunction "C_3") (pintype "passive"))
      (node (ref "R354") (pin "P$2") (pinfunction "2_P$2") (pintype "passive"))
      (node (ref "R47") (pin "P$2") (pinfunction "2_P$2") (pintype "passive"))
    )
    (net (code "57") (name "Net-(Q322-C)") (class "Default")
      (node (ref "C314") (pin "1") (pinfunction "1_1") (pintype "passive"))
      (node (ref "D316") (pin "A") (pinfunction "A_A") (pintype "passive"))
      (node (ref "Q322") (pin "3") (pinfunction "C_3") (pintype "passive"))
      (node (ref "Q323") (pin "2") (pinfunction "B_2") (pintype "passive"))
      (node (ref "R353") (pin "P$2") (pinfunction "2_P$2") (pintype "passive"))
    )
    (net (code "58") (name "Net-(Q323-E)") (class "Default")
      (node (ref "Q323") (pin "1") (pinfunction "E_1") (pintype "passive"))
      (node (ref "R355") (pin "P$2") (pinfunction "2_P$2") (pintype "passive"))
    )
    (net (code "59") (name "Net-(Q324-B)") (class "Default")
      (node (ref "Q324") (pin "2") (pinfunction "B_2") (pintype "passive"))
      (node (ref "R356") (pin "P$2") (pinfunction "2_P$2") (pintype "passive"))
    )
    (net (code "60") (name "Net-(Q324-C)") (class "Default")
      (node (ref "LED1") (pin "A") (pinfunction "A_A") (pintype "passive"))
      (node (ref "Q324") (pin "3") (pinfunction "C_3") (pintype "passive"))
      (node (ref "R360") (pin "P$1") (pinfunction "1_P$1") (pintype "passive"))
    )
    (net (code "61") (name "Net-(Q324-E)") (class "Default")
      (node (ref "Q324") (pin "1") (pinfunction "E_1") (pintype "passive"))
      (node (ref "R357") (pin "P$2") (pinfunction "2_P$2") (pintype "passive"))
    )
    (net (code "62") (name "Net-(Q325-B)") (class "Default")
      (node (ref "Q325") (pin "2") (pinfunction "B_2") (pintype "passive"))
      (node (ref "R360") (pin "P$2") (pinfunction "2_P$2") (pintype "passive"))
    )
    (net (code "63") (name "Net-(Q325-C)") (class "Default")
      (node (ref "LED2") (pin "A") (pinfunction "A_A") (pintype "passive"))
      (node (ref "Q325") (pin "3") (pinfunction "C_3") (pintype "passive"))
      (node (ref "R359") (pin "P$2") (pinfunction "2_P$2") (pintype "passive"))
    )
    (net (code "64") (name "Net-(R300-1)") (class "Default")
      (node (ref "JP2") (pin "3") (pinfunction "3_3") (pintype "passive"))
      (node (ref "R300") (pin "P$1") (pinfunction "1_P$1") (pintype "passive"))
    )
    (net (code "65") (name "Net-(R300-2)") (class "Default")
      (node (ref "C301") (pin "1") (pinfunction "1_1") (pintype "passive"))
      (node (ref "C302") (pin "2") (pinfunction "2_2") (pintype "passive"))
      (node (ref "R300") (pin "P$2") (pinfunction "2_P$2") (pintype "passive"))
      (node (ref "R301") (pin "P$2") (pinfunction "2_P$2") (pintype "passive"))
    )
    (net (code "66") (name "Net-(R303-1)") (class "Default")
      (node (ref "R303") (pin "P$1") (pinfunction "1_P$1") (pintype "passive"))
      (node (ref "R304") (pin "P$1") (pinfunction "1_P$1") (pintype "passive"))
    )
    (net (code "67") (name "Net-(R305-2)") (class "Default")
      (node (ref "C308") (pin "1") (pinfunction "1_1") (pintype "passive"))
      (node (ref "D301") (pin "A") (pinfunction "A_A") (pintype "passive"))
      (node (ref "R305") (pin "P$2") (pinfunction "2_P$2") (pintype "passive"))
      (node (ref "R306") (pin "P$1") (pinfunction "1_P$1") (pintype "passive"))
      (node (ref "R307") (pin "P$1") (pinfunction "1_P$1") (pintype "passive"))
      (node (ref "R318") (pin "P$2") (pinfunction "2_P$2") (pintype "passive"))
      (node (ref "R323") (pin "P$2") (pinfunction "2_P$2") (pintype "passive"))
    )
    (net (code "68") (name "Net-(R308-1)") (class "Default")
      (node (ref "R308") (pin "P$1") (pinfunction "1_P$1") (pintype "passive"))
      (node (ref "R312") (pin "P$1") (pinfunction "1_P$1") (pintype "passive"))
      (node (ref "R313") (pin "P$1") (pinfunction "1_P$1") (pintype "passive"))
    )
    (net (code "69") (name "Net-(R309-1)") (class "Default")
      (node (ref "R309") (pin "P$1") (pinfunction "1_P$1") (pintype "passive"))
      (node (ref "R310") (pin "P$1") (pinfunction "1_P$1") (pintype "passive"))
      (node (ref "R311") (pin "P$2") (pinfunction "2_P$2") (pintype "passive"))
    )
    (net (code "70") (name "Net-(R319-1)") (class "Default")
      (node (ref "R319") (pin "P$1") (pinfunction "1_P$1") (pintype "passive"))
      (node (ref "R320") (pin "P$2") (pinfunction "2_P$2") (pintype "passive"))
      (node (ref "R324") (pin "P$1") (pinfunction "1_P$1") (pintype "passive"))
    )
    (net (code "71") (name "Net-(R321-1)") (class "Default")
      (node (ref "R321") (pin "P$1") (pinfunction "1_P$1") (pintype "passive"))
      (node (ref "VR3") (pin "2") (pinfunction "E_2") (pintype "passive"))
    )
    (net (code "72") (name "Net-(R325-2)") (class "Default")
      (node (ref "C309") (pin "2") (pinfunction "2_2") (pintype "passive"))
      (node (ref "D305") (pin "A") (pinfunction "A_A") (pintype "passive"))
      (node (ref "D306") (pin "C") (pinfunction "C_C") (pintype "passive"))
      (node (ref "R325") (pin "P$2") (pinfunction "2_P$2") (pintype "passive"))
      (node (ref "R326") (pin "P$1") (pinfunction "1_P$1") (pintype "passive"))
      (node (ref "R344") (pin "P$1") (pinfunction "1_P$1") (pintype "passive"))
      (node (ref "R346") (pin "P$2") (pinfunction "2_P$2") (pintype "passive"))
      (node (ref "RHUGE1") (pin "P$2") (pinfunction "2_P$2") (pintype "passive"))
      (node (ref "RHUGE2") (pin "P$2") (pinfunction "2_P$2") (pintype "passive"))
      (node (ref "RHUGE3") (pin "P$1") (pinfunction "1_P$1") (pintype "passive"))
      (node (ref "RHUGE4") (pin "P$1") (pinfunction "1_P$1") (pintype "passive"))
      (node (ref "U$1") (pin "3") (pinfunction "NO_3") (pintype "bidirectional"))
    )
    (net (code "73") (name "Net-(R328-1)") (class "Default")
      (node (ref "R328") (pin "P$1") (pinfunction "1_P$1") (pintype "passive"))
      (node (ref "R3XX1") (pin "P$2") (pinfunction "2_P$2") (pintype "passive"))
    )
    (net (code "74") (name "Net-(R338-2)") (class "Default")
      (node (ref "JP2") (pin "5") (pinfunction "5_5") (pintype "passive"))
      (node (ref "R338") (pin "P$2") (pinfunction "2_P$2") (pintype "passive"))
    )
    (net (code "75") (name "Net-(R339-2)") (class "Default")
      (node (ref "JP2") (pin "6") (pinfunction "6_6") (pintype "passive"))
      (node (ref "R339") (pin "P$2") (pinfunction "2_P$2") (pintype "passive"))
    )
    (net (code "76") (name "Net-(R344-2)") (class "Default")
      (node (ref "C311") (pin "1") (pinfunction "1_1") (pintype "passive"))
      (node (ref "D309") (pin "C") (pinfunction "C_C") (pintype "passive"))
      (node (ref "D310") (pin "A") (pinfunction "A_A") (pintype "passive"))
      (node (ref "R344") (pin "P$2") (pinfunction "2_P$2") (pintype "passive"))
    )
    (net (code "77") (name "Net-(R345-1)") (class "Default")
      (node (ref "C311A") (pin "1") (pinfunction "1_1") (pintype "passive"))
      (node (ref "D311") (pin "C") (pinfunction "C_C") (pintype "passive"))
      (node (ref "D312") (pin "A") (pinfunction "A_A") (pintype "passive"))
      (node (ref "R345") (pin "P$1") (pinfunction "1_P$1") (pintype "passive"))
    )
    (net (code "78") (name "Net-(R347-1)") (class "Default")
      (node (ref "CEXPLODED") (pin "1") (pinfunction "1_1") (pintype "passive"))
      (node (ref "R347") (pin "P$1") (pinfunction "1_P$1") (pintype "passive"))
    )
    (net (code "79") (name "Net-(R349-1)") (class "Default")
      (node (ref "C312") (pin "1") (pinfunction "1_1") (pintype "passive"))
      (node (ref "R349") (pin "P$1") (pinfunction "1_P$1") (pintype "passive"))
    )
    (net (code "80") (name "Net-(R352-2)") (class "Default")
      (node (ref "D316") (pin "C") (pinfunction "C_C") (pintype "passive"))
      (node (ref "R352") (pin "P$2") (pinfunction "2_P$2") (pintype "passive"))
    )
    (net (code "81") (name "Net-(R358-2)") (class "Default")
      (node (ref "D313") (pin "C") (pinfunction "C_C") (pintype "passive"))
      (node (ref "R358") (pin "P$2") (pinfunction "2_P$2") (pintype "passive"))
      (node (ref "U$1") (pin "5") (pinfunction "COIL1_5") (pintype "bidirectional"))
    )
    (net (code "82") (name "Net-(R374-1)") (class "Default")
      (node (ref "D308") (pin "A") (pinfunction "A_A") (pintype "passive"))
      (node (ref "R374") (pin "P$1") (pinfunction "1_P$1") (pintype "passive"))
    )
    (net (code "83") (name "V+") (class "Default")
      (node (ref "D305") (pin "C") (pinfunction "C_C") (pintype "passive"))
      (node (ref "Q310") (pin "3") (pinfunction "C_3") (pintype "passive"))
      (node (ref "Q312") (pin "3") (pinfunction "C_3") (pintype "passive"))
      (node (ref "Q314") (pin "3") (pinfunction "C_3") (pintype "passive"))
      (node (ref "Q316") (pin "3") (pinfunction "C_3") (pintype "passive"))
      (node (ref "R338") (pin "P$1") (pinfunction "1_P$1") (pintype "passive"))
    )
    (net (code "84") (name "V-") (class "Default")
      (node (ref "Q313") (pin "3") (pinfunction "C_3") (pintype "passive"))
      (node (ref "Q315") (pin "3") (pinfunction "C_3") (pintype "passive"))
      (node (ref "Q317") (pin "3") (pinfunction "C_3") (pintype "passive"))
      (node (ref "R322") (pin "P$2") (pinfunction "2_P$2") (pintype "passive"))
      (node (ref "R339") (pin "P$1") (pinfunction "1_P$1") (pintype "passive"))
    )
    (net (code "85") (name "unconnected-(C1-Pad1)") (class "Default")
      (node (ref "C1") (pin "1") (pinfunction "1_1") (pintype "passive"))
    )
    (net (code "86") (name "unconnected-(C1-Pad2)") (class "Default")
      (node (ref "C1") (pin "2") (pinfunction "2_2") (pintype "passive"))
    )
    (net (code "87") (name "unconnected-(D306-PadA)") (class "Default")
      (node (ref "D306") (pin "A") (pinfunction "A_A") (pintype "passive"))
    )
    (net (code "88") (name "unconnected-(JP1-Pad1)") (class "Default")
      (node (ref "JP1") (pin "1") (pinfunction "1_1") (pintype "passive"))
    )
    (net (code "89") (name "unconnected-(JP1-Pad2)") (class "Default")
      (node (ref "JP1") (pin "2") (pinfunction "2_2") (pintype "passive"))
    )
    (net (code "90") (name "unconnected-(JP1-Pad3)") (class "Default")
      (node (ref "JP1") (pin "3") (pinfunction "3_3") (pintype "passive"))
    )
    (net (code "91") (name "unconnected-(JP1-Pad4)") (class "Default")
      (node (ref "JP1") (pin "4") (pinfunction "4_4") (pintype "passive"))
    )
    (net (code "92") (name "unconnected-(JP1-Pad5)") (class "Default")
      (node (ref "JP1") (pin "5") (pinfunction "5_5") (pintype "passive"))
    )
    (net (code "93") (name "unconnected-(JP1-Pad6)") (class "Default")
      (node (ref "JP1") (pin "6") (pinfunction "6_6") (pintype "passive"))
    )
    (net (code "94") (name "unconnected-(JP2-Pad1)") (class "Default")
      (node (ref "JP2") (pin "1") (pinfunction "1_1") (pintype "passive"))
    )
    (net (code "95") (name "unconnected-(JP2-Pad2)") (class "Default")
      (node (ref "JP2") (pin "2") (pinfunction "2_2") (pintype "passive"))
    )
    (net (code "96") (name "unconnected-(JP2-Pad4)") (class "Default")
      (node (ref "JP2") (pin "4") (pinfunction "4_4") (pintype "passive"))
    )
    (net (code "97") (name "unconnected-(JP2-Pad7)") (class "Default")
      (node (ref "JP2") (pin "7") (pinfunction "7_7") (pintype "passive"))
    )
    (net (code "98") (name "unconnected-(Q0-B-Pad2)") (class "Default")
      (node (ref "Q0") (pin "2") (pinfunction "B_2") (pintype "passive"))
    )
    (net (code "99") (name "unconnected-(Q0-C-Pad3)") (class "Default")
      (node (ref "Q0") (pin "3") (pinfunction "C_3") (pintype "passive"))
    )
    (net (code "100") (name "unconnected-(Q0-E-Pad1)") (class "Default")
      (node (ref "Q0") (pin "1") (pinfunction "E_1") (pintype "passive"))
    )
    (net (code "101") (name "unconnected-(Q1-B-Pad2)") (class "Default")
      (node (ref "Q1") (pin "2") (pinfunction "B_2") (pintype "passive"))
    )
    (net (code "102") (name "unconnected-(Q1-C-Pad3)") (class "Default")
      (node (ref "Q1") (pin "3") (pinfunction "C_3") (pintype "passive"))
    )
    (net (code "103") (name "unconnected-(Q1-E-Pad1)") (class "Default")
      (node (ref "Q1") (pin "1") (pinfunction "E_1") (pintype "passive"))
    )
    (net (code "104") (name "unconnected-(Q311-C-Pad3)") (class "Default")
      (node (ref "Q311") (pin "3") (pinfunction "C_3") (pintype "passive"))
    )
    (net (code "105") (name "unconnected-(Q311-E-Pad1)") (class "Default")
      (node (ref "Q311") (pin "1") (pinfunction "E_1") (pintype "passive"))
    )
    (net (code "106") (name "unconnected-(Q313-B-Pad2)") (class "Default")
      (node (ref "Q313") (pin "2") (pinfunction "B_2") (pintype "passive"))
    )
    (net (code "107") (name "unconnected-(Q322-E-Pad1)") (class "Default")
      (node (ref "Q322") (pin "1") (pinfunction "E_1") (pintype "passive"))
    )
    (net (code "108") (name "unconnected-(Q326-B-Pad2)") (class "Default")
      (node (ref "Q326") (pin "2") (pinfunction "B_2") (pintype "passive"))
    )
    (net (code "109") (name "unconnected-(Q326-C-Pad3)") (class "Default")
      (node (ref "Q326") (pin "3") (pinfunction "C_3") (pintype "passive"))
    )
    (net (code "110") (name "unconnected-(Q326-E-Pad1)") (class "Default")
      (node (ref "Q326") (pin "1") (pinfunction "E_1") (pintype "passive"))
    )
    (net (code "111") (name "unconnected-(R1-1-PadP$1)") (class "Default")
      (node (ref "R1") (pin "P$1") (pinfunction "1_P$1") (pintype "passive"))
    )
    (net (code "112") (name "unconnected-(R1-2-PadP$2)") (class "Default")
      (node (ref "R1") (pin "P$2") (pinfunction "2_P$2") (pintype "passive"))
    )
    (net (code "113") (name "unconnected-(R47-1-PadP$1)") (class "Default")
      (node (ref "R47") (pin "P$1") (pinfunction "1_P$1") (pintype "passive"))
    )
    (net (code "114") (name "unconnected-(R323-1-PadP$1)") (class "Default")
      (node (ref "R323") (pin "P$1") (pinfunction "1_P$1") (pintype "passive"))
    )
    (net (code "115") (name "unconnected-(R326-2-PadP$2)") (class "Default")
      (node (ref "R326") (pin "P$2") (pinfunction "2_P$2") (pintype "passive"))
    )
    (net (code "116") (name "unconnected-(R353-1-PadP$1)") (class "Default")
      (node (ref "R353") (pin "P$1") (pinfunction "1_P$1") (pintype "passive"))
    )
    (net (code "117") (name "unconnected-(R361-1-PadP$1)") (class "Default")
      (node (ref "R361") (pin "P$1") (pinfunction "1_P$1") (pintype "passive"))
    )
    (net (code "118") (name "unconnected-(R362-1-PadP$1)") (class "Default")
      (node (ref "R362") (pin "P$1") (pinfunction "1_P$1") (pintype "passive"))
    )
    (net (code "119") (name "unconnected-(R363-1-PadP$1)") (class "Default")
      (node (ref "R363") (pin "P$1") (pinfunction "1_P$1") (pintype "passive"))
    )
    (net (code "120") (name "unconnected-(R363-2-PadP$2)") (class "Default")
      (node (ref "R363") (pin "P$2") (pinfunction "2_P$2") (pintype "passive"))
    )
    (net (code "121") (name "unconnected-(R364-1-PadP$1)") (class "Default")
      (node (ref "R364") (pin "P$1") (pinfunction "1_P$1") (pintype "passive"))
    )
    (net (code "122") (name "unconnected-(R364-2-PadP$2)") (class "Default")
      (node (ref "R364") (pin "P$2") (pinfunction "2_P$2") (pintype "passive"))
    )
    (net (code "123") (name "unconnected-(R372-1-PadP$1)") (class "Default")
      (node (ref "R372") (pin "P$1") (pinfunction "1_P$1") (pintype "passive"))
    )
    (net (code "124") (name "unconnected-(U$1-MAIN-Pad2)") (class "Default")
      (node (ref "U$1") (pin "2") (pinfunction "MAIN_2") (pintype "bidirectional"))
    )
    (net (code "125") (name "unconnected-(U$1-NC-Pad4)") (class "Default")
      (node (ref "U$1") (pin "4") (pinfunction "NC_4") (pintype "bidirectional"))
    )
    (net (code "126") (name "unconnected-(Z302-PadA)") (class "Default")
      (node (ref "Z302") (pin "A") (pinfunction "A_A") (pintype "passive"))
    )
    (net (code "127") (name "unconnected-(Z302-PadC)") (class "Default")
      (node (ref "Z302") (pin "C") (pinfunction "C_C") (pintype "passive"))
    )
  )
)
